# BG_Sch.net
KiCad netlist of a schematic drawn in Altium Designer
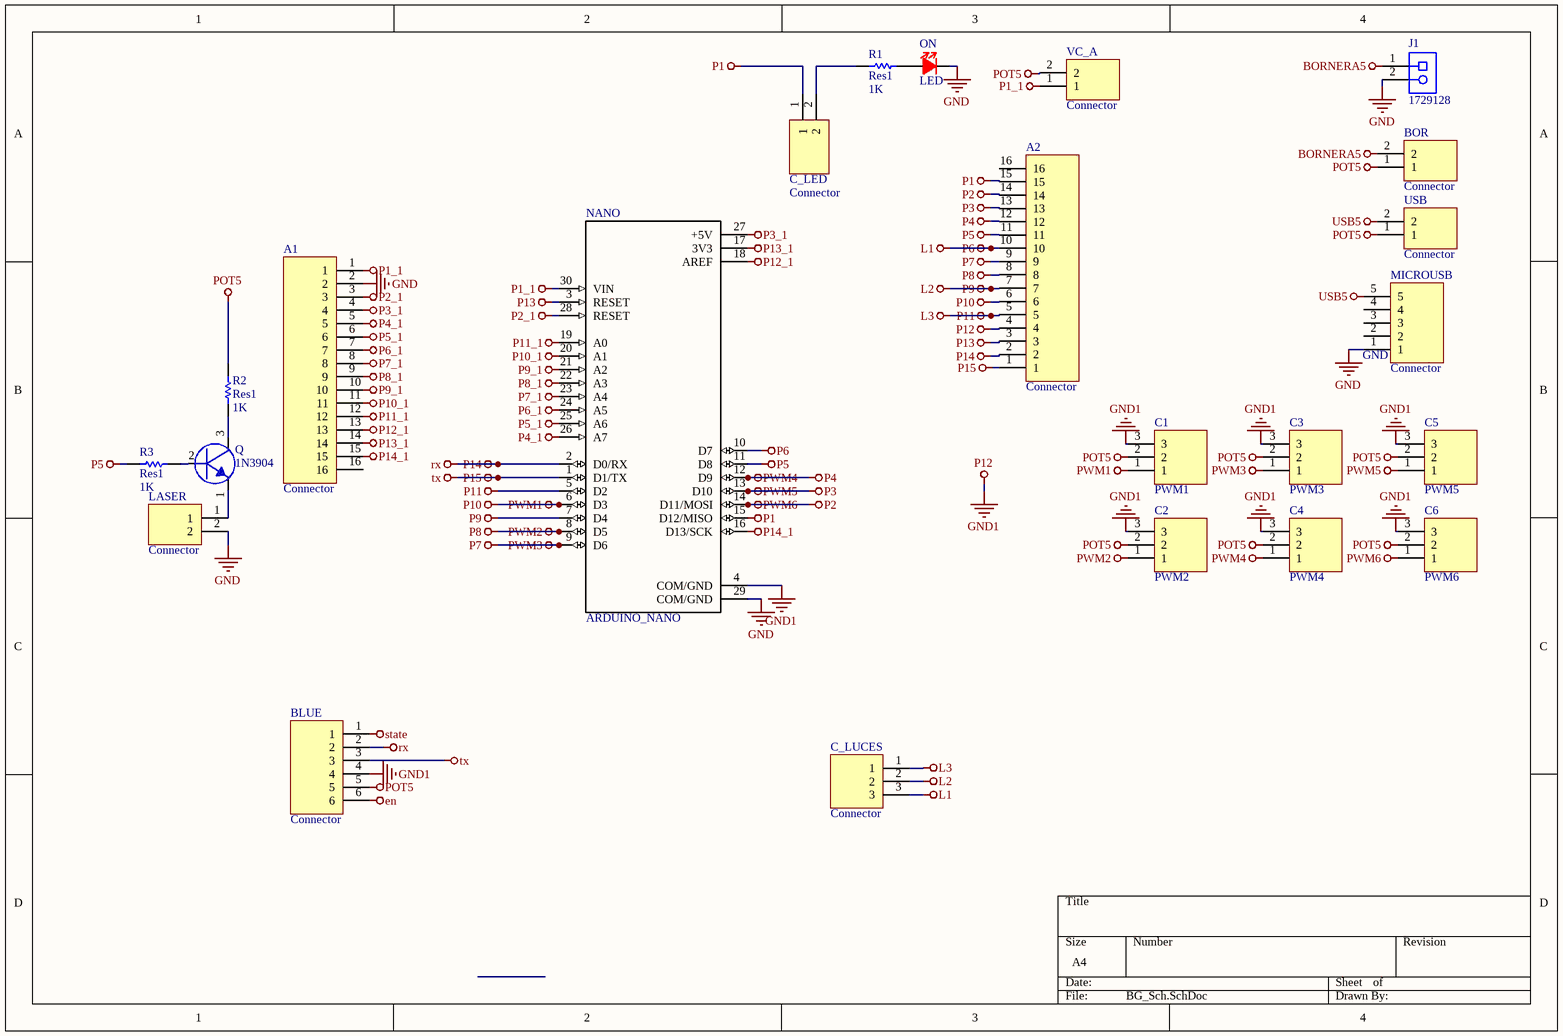
[diagram p0: BG_Sch.SchDoc]

(export (version "E")
  (design (tool "Eeschema 10.0.6"))
  (components
    (comp (ref "A1")
      (value "Connector")
      (footprint "1x16x2.54 Pin Header TH V")
      (libsource (lib "IFS_Altium") (part "Header 1x16"))
    )
    (comp (ref "A2")
      (value "Connector")
      (footprint "1x16x2.54 Pin Header TH V")
      (libsource (lib "") (part "Header 1x16_1"))
    )
    (comp (ref "BLUE")
      (value "Connector")
      (footprint "1x6x2.54 Pin Header TH V")
      (libsource (lib "IFS_Altium") (part "Header 1x6"))
    )
    (comp (ref "BOR")
      (value "Connector")
      (footprint "1x2x2.54 Pin Header TH V")
      (libsource (lib "IFS_Altium") (part "Header 1x2"))
    )
    (comp (ref "C1")
      (value "PWM1")
      (footprint "1x3x2.54 Pin Header TH V")
      (libsource (lib "IFS_Altium") (part "Header 1x3"))
    )
    (comp (ref "C2")
      (value "PWM2")
      (footprint "1x3x2.54 Pin Header TH V")
      (libsource (lib "IFS_Altium") (part "Header 1x3"))
    )
    (comp (ref "C3")
      (value "PWM3")
      (footprint "1x3x2.54 Pin Header TH V")
      (libsource (lib "IFS_Altium") (part "Header 1x3"))
    )
    (comp (ref "C4")
      (value "PWM4")
      (footprint "1x3x2.54 Pin Header TH V")
      (libsource (lib "IFS_Altium") (part "Header 1x3"))
    )
    (comp (ref "C5")
      (value "PWM5")
      (footprint "1x3x2.54 Pin Header TH V")
      (libsource (lib "IFS_Altium") (part "Header 1x3"))
    )
    (comp (ref "C6")
      (value "PWM6")
      (footprint "1x3x2.54 Pin Header TH V")
      (libsource (lib "IFS_Altium") (part "Header 1x3"))
    )
    (comp (ref "C_LED")
      (value "Connector")
      (footprint "1x2x2.54 Pin Header TH V")
      (libsource (lib "") (part "Header 1x2_1"))
    )
    (comp (ref "C_LUCES")
      (value "Connector")
      (footprint "1x3x2.54 Pin Header TH V")
      (libsource (lib "CARO") (part "Header 1x3"))
    )
    (comp (ref "J1")
      (value "1729128")
      (footprint "PHOE-1729128-2_V")
      (description "PCB Terminal Block, 13.5 A, 400 V, 2-Pin THD, RoHS, Bulk")
      (fields (field (name "MANUFACTURER") "Phoenix Contact"))
      (libsource (lib "Altium Content Vault") (part "CN-2P-F-R2"))
    )
    (comp (ref "LASER")
      (value "Connector")
      (footprint "1x2x2.54 Pin Header TH V")
      (libsource (lib "CARO") (part "Header 1x2"))
    )
    (comp (ref "MICROUSB")
      (value "Connector")
      (footprint "1x5x2.54 Pin Header TH V")
      (libsource (lib "IFS_Altium") (part "Header 1x5"))
    )
    (comp (ref "NANO")
      (value "ARDUINO_NANO")
      (footprint "*SHIELD_ARDUINO_NANO")
      (description "ATmega328 Arduino Nano AVRÂ® ATmega AVR MCU 8-Bit Embedded Evaluation Board")
      (fields (field (name "MP") "ARDUINO NANO") (field (name "MF") "Arduino"))
      (libsource (lib "Mercury") (part "ARDUINO_NANO"))
    )
    (comp (ref "ON")
      (value "LED")
      (footprint "LED Red 3mm TH V")
      (description "LED Red")
      (libsource (lib "IFS_Altium") (part "LED Red"))
    )
    (comp (ref "Q")
      (value "1N3904")
      (footprint "TO92-2.54")
      (description "1N3904 NPN Transistor")
      (libsource (lib "IFS_Altium") (part "1N3904"))
    )
    (comp (ref "R1")
      (value "Res1")
      (footprint "AXIAL-0.3")
      (description "Resistor")
      (fields (field (name "ALTIUM_VALUE") "1K") (field (name "PUBLISHER") "Altium Limited"))
      (libsource (lib "Miscellaneous Devices") (part "Res1"))
    )
    (comp (ref "R2")
      (value "Res1")
      (footprint "AXIAL-0.3")
      (description "Resistor")
      (fields (field (name "ALTIUM_VALUE") "1K") (field (name "PUBLISHER") "Altium Limited"))
      (libsource (lib "Miscellaneous Devices") (part "Res1"))
    )
    (comp (ref "R3")
      (value "Res1")
      (footprint "AXIAL-0.3")
      (description "Resistor")
      (fields (field (name "ALTIUM_VALUE") "1K") (field (name "PUBLISHER") "Altium Limited"))
      (libsource (lib "Miscellaneous Devices") (part "Res1"))
    )
    (comp (ref "USB")
      (value "Connector")
      (footprint "1x2x2.54 Pin Header TH V")
      (libsource (lib "IFS_Altium") (part "Header 1x2"))
    )
    (comp (ref "VC_A")
      (value "Connector")
      (footprint "1x2x2.54 Pin Header TH V")
      (libsource (lib "IFS_Altium") (part "Header 1x2"))
    )
  )
  (nets
    (net (code "1") (name "BORNERA5") (class "Default")
      (node (ref "BOR") (pin "2") (pinfunction "2_2") (pintype "passive"))
      (node (ref "J1") (pin "1") (pinfunction "1_1") (pintype "passive"))
    )
    (net (code "2") (name "GND") (class "Default")
      (node (ref "A1") (pin "2") (pinfunction "2_2") (pintype "passive"))
      (node (ref "J1") (pin "2") (pinfunction "2_2") (pintype "passive"))
      (node (ref "LASER") (pin "2") (pinfunction "2_2") (pintype "passive"))
      (node (ref "MICROUSB") (pin "1") (pinfunction "1_1") (pintype "passive"))
      (node (ref "NANO") (pin "29") (pinfunction "COM/GND_29") (pintype "power_in"))
      (node (ref "ON") (pin "1") (pinfunction "1_1") (pintype "passive"))
    )
    (net (code "3") (name "GND1") (class "Default")
      (node (ref "A2") (pin "4") (pinfunction "4_4") (pintype "passive"))
      (node (ref "BLUE") (pin "4") (pinfunction "4_4") (pintype "passive"))
      (node (ref "C1") (pin "3") (pinfunction "3_3") (pintype "passive"))
      (node (ref "C2") (pin "3") (pinfunction "3_3") (pintype "passive"))
      (node (ref "C3") (pin "3") (pinfunction "3_3") (pintype "passive"))
      (node (ref "C4") (pin "3") (pinfunction "3_3") (pintype "passive"))
      (node (ref "C5") (pin "3") (pinfunction "3_3") (pintype "passive"))
      (node (ref "C6") (pin "3") (pinfunction "3_3") (pintype "passive"))
      (node (ref "NANO") (pin "4") (pinfunction "COM/GND_4") (pintype "power_in"))
    )
    (net (code "4") (name "L1") (class "Default")
      (node (ref "A2") (pin "10") (pinfunction "10_10") (pintype "passive"))
      (node (ref "C_LUCES") (pin "3") (pinfunction "3_3") (pintype "passive"))
      (node (ref "NANO") (pin "10") (pinfunction "D7_10") (pintype "bidirectional"))
    )
    (net (code "5") (name "L2") (class "Default")
      (node (ref "A2") (pin "7") (pinfunction "7_7") (pintype "passive"))
      (node (ref "C_LUCES") (pin "2") (pinfunction "2_2") (pintype "passive"))
      (node (ref "NANO") (pin "7") (pinfunction "D4_7") (pintype "bidirectional"))
    )
    (net (code "6") (name "L3") (class "Default")
      (node (ref "A2") (pin "5") (pinfunction "5_5") (pintype "passive"))
      (node (ref "C_LUCES") (pin "1") (pinfunction "1_1") (pintype "passive"))
      (node (ref "NANO") (pin "5") (pinfunction "D2_5") (pintype "bidirectional"))
    )
    (net (code "7") (name "Net-(C_LED-Pad2)") (class "Default")
      (node (ref "C_LED") (pin "2") (pinfunction "2_2") (pintype "passive"))
      (node (ref "R1") (pin "1") (pinfunction "1_1") (pintype "passive"))
    )
    (net (code "8") (name "Net-(LASER-Pad1)") (class "Default")
      (node (ref "LASER") (pin "1") (pinfunction "1_1") (pintype "passive"))
      (node (ref "Q") (pin "1") (pinfunction "1_1") (pintype "passive"))
    )
    (net (code "9") (name "Net-(ON-Pad2)") (class "Default")
      (node (ref "ON") (pin "2") (pinfunction "2_2") (pintype "passive"))
      (node (ref "R1") (pin "2") (pinfunction "2_2") (pintype "passive"))
    )
    (net (code "10") (name "Net-(Q-Pad2)") (class "Default")
      (node (ref "Q") (pin "2") (pinfunction "2_2") (pintype "passive"))
      (node (ref "R3") (pin "2") (pinfunction "2_2") (pintype "passive"))
    )
    (net (code "11") (name "Net-(Q-Pad3)") (class "Default")
      (node (ref "Q") (pin "3") (pinfunction "3_3") (pintype "passive"))
      (node (ref "R2") (pin "1") (pinfunction "1_1") (pintype "passive"))
    )
    (net (code "12") (name "P1") (class "Default")
      (node (ref "A2") (pin "15") (pinfunction "15_15") (pintype "passive"))
      (node (ref "C_LED") (pin "1") (pinfunction "1_1") (pintype "passive"))
      (node (ref "NANO") (pin "15") (pinfunction "D12/MISO_15") (pintype "bidirectional"))
    )
    (net (code "13") (name "P1_1") (class "Default")
      (node (ref "A1") (pin "1") (pinfunction "1_1") (pintype "passive"))
      (node (ref "NANO") (pin "30") (pinfunction "VIN_30") (pintype "input"))
      (node (ref "VC_A") (pin "1") (pinfunction "1_1") (pintype "passive"))
    )
    (net (code "14") (name "P2") (class "Default")
      (node (ref "A2") (pin "14") (pinfunction "14_14") (pintype "passive"))
      (node (ref "C6") (pin "1") (pinfunction "1_1") (pintype "passive"))
      (node (ref "NANO") (pin "14") (pinfunction "D11/MOSI_14") (pintype "bidirectional"))
    )
    (net (code "15") (name "P2_1") (class "Default")
      (node (ref "A1") (pin "3") (pinfunction "3_3") (pintype "passive"))
      (node (ref "NANO") (pin "28") (pinfunction "RESET_28") (pintype "input"))
    )
    (net (code "16") (name "P3") (class "Default")
      (node (ref "A2") (pin "13") (pinfunction "13_13") (pintype "passive"))
      (node (ref "C5") (pin "1") (pinfunction "1_1") (pintype "passive"))
      (node (ref "NANO") (pin "13") (pinfunction "D10_13") (pintype "bidirectional"))
    )
    (net (code "17") (name "P3_1") (class "Default")
      (node (ref "A1") (pin "4") (pinfunction "4_4") (pintype "passive"))
      (node (ref "NANO") (pin "27") (pinfunction "+5V_27") (pintype "power_in"))
    )
    (net (code "18") (name "P4") (class "Default")
      (node (ref "A2") (pin "12") (pinfunction "12_12") (pintype "passive"))
      (node (ref "C4") (pin "1") (pinfunction "1_1") (pintype "passive"))
      (node (ref "NANO") (pin "12") (pinfunction "D9_12") (pintype "bidirectional"))
    )
    (net (code "19") (name "P4_1") (class "Default")
      (node (ref "A1") (pin "5") (pinfunction "5_5") (pintype "passive"))
      (node (ref "NANO") (pin "26") (pinfunction "A7_26") (pintype "input"))
    )
    (net (code "20") (name "P5") (class "Default")
      (node (ref "A2") (pin "11") (pinfunction "11_11") (pintype "passive"))
      (node (ref "NANO") (pin "11") (pinfunction "D8_11") (pintype "bidirectional"))
      (node (ref "R3") (pin "1") (pinfunction "1_1") (pintype "passive"))
    )
    (net (code "21") (name "P5_1") (class "Default")
      (node (ref "A1") (pin "6") (pinfunction "6_6") (pintype "passive"))
      (node (ref "NANO") (pin "25") (pinfunction "A6_25") (pintype "input"))
    )
    (net (code "22") (name "P6_1") (class "Default")
      (node (ref "A1") (pin "7") (pinfunction "7_7") (pintype "passive"))
      (node (ref "NANO") (pin "24") (pinfunction "A5_24") (pintype "input"))
    )
    (net (code "23") (name "P7") (class "Default")
      (node (ref "A2") (pin "9") (pinfunction "9_9") (pintype "passive"))
      (node (ref "C3") (pin "1") (pinfunction "1_1") (pintype "passive"))
      (node (ref "NANO") (pin "9") (pinfunction "D6_9") (pintype "bidirectional"))
    )
    (net (code "24") (name "P7_1") (class "Default")
      (node (ref "A1") (pin "8") (pinfunction "8_8") (pintype "passive"))
      (node (ref "NANO") (pin "23") (pinfunction "A4_23") (pintype "input"))
    )
    (net (code "25") (name "P8") (class "Default")
      (node (ref "A2") (pin "8") (pinfunction "8_8") (pintype "passive"))
      (node (ref "C2") (pin "1") (pinfunction "1_1") (pintype "passive"))
      (node (ref "NANO") (pin "8") (pinfunction "D5_8") (pintype "bidirectional"))
    )
    (net (code "26") (name "P8_1") (class "Default")
      (node (ref "A1") (pin "9") (pinfunction "9_9") (pintype "passive"))
      (node (ref "NANO") (pin "22") (pinfunction "A3_22") (pintype "input"))
    )
    (net (code "27") (name "P9_1") (class "Default")
      (node (ref "A1") (pin "10") (pinfunction "10_10") (pintype "passive"))
      (node (ref "NANO") (pin "21") (pinfunction "A2_21") (pintype "input"))
    )
    (net (code "28") (name "P10") (class "Default")
      (node (ref "A2") (pin "6") (pinfunction "6_6") (pintype "passive"))
      (node (ref "C1") (pin "1") (pinfunction "1_1") (pintype "passive"))
      (node (ref "NANO") (pin "6") (pinfunction "D3_6") (pintype "bidirectional"))
    )
    (net (code "29") (name "P10_1") (class "Default")
      (node (ref "A1") (pin "11") (pinfunction "11_11") (pintype "passive"))
      (node (ref "NANO") (pin "20") (pinfunction "A1_20") (pintype "input"))
    )
    (net (code "30") (name "P11_1") (class "Default")
      (node (ref "A1") (pin "12") (pinfunction "12_12") (pintype "passive"))
      (node (ref "NANO") (pin "19") (pinfunction "A0_19") (pintype "input"))
    )
    (net (code "31") (name "P12_1") (class "Default")
      (node (ref "A1") (pin "13") (pinfunction "13_13") (pintype "passive"))
      (node (ref "NANO") (pin "18") (pinfunction "AREF_18") (pintype "power_in"))
    )
    (net (code "32") (name "P13") (class "Default")
      (node (ref "A2") (pin "3") (pinfunction "3_3") (pintype "passive"))
      (node (ref "NANO") (pin "3") (pinfunction "RESET_3") (pintype "input"))
    )
    (net (code "33") (name "P13_1") (class "Default")
      (node (ref "A1") (pin "14") (pinfunction "14_14") (pintype "passive"))
      (node (ref "NANO") (pin "17") (pinfunction "3V3_17") (pintype "power_in"))
    )
    (net (code "34") (name "P14") (class "Default")
      (node (ref "A2") (pin "2") (pinfunction "2_2") (pintype "passive"))
      (node (ref "BLUE") (pin "2") (pinfunction "2_2") (pintype "passive"))
      (node (ref "NANO") (pin "2") (pinfunction "D0/RX_2") (pintype "bidirectional"))
    )
    (net (code "35") (name "P14_1") (class "Default")
      (node (ref "A1") (pin "15") (pinfunction "15_15") (pintype "passive"))
      (node (ref "NANO") (pin "16") (pinfunction "D13/SCK_16") (pintype "bidirectional"))
    )
    (net (code "36") (name "P15") (class "Default")
      (node (ref "A2") (pin "1") (pinfunction "1_1") (pintype "passive"))
      (node (ref "BLUE") (pin "3") (pinfunction "3_3") (pintype "passive"))
      (node (ref "NANO") (pin "1") (pinfunction "D1/TX_1") (pintype "bidirectional"))
    )
    (net (code "37") (name "POT5") (class "Default")
      (node (ref "BLUE") (pin "5") (pinfunction "5_5") (pintype "passive"))
      (node (ref "BOR") (pin "1") (pinfunction "1_1") (pintype "passive"))
      (node (ref "C1") (pin "2") (pinfunction "2_2") (pintype "passive"))
      (node (ref "C2") (pin "2") (pinfunction "2_2") (pintype "passive"))
      (node (ref "C3") (pin "2") (pinfunction "2_2") (pintype "passive"))
      (node (ref "C4") (pin "2") (pinfunction "2_2") (pintype "passive"))
      (node (ref "C5") (pin "2") (pinfunction "2_2") (pintype "passive"))
      (node (ref "C6") (pin "2") (pinfunction "2_2") (pintype "passive"))
      (node (ref "R2") (pin "2") (pinfunction "2_2") (pintype "passive"))
      (node (ref "USB") (pin "1") (pinfunction "1_1") (pintype "passive"))
      (node (ref "VC_A") (pin "2") (pinfunction "2_2") (pintype "passive"))
    )
    (net (code "38") (name "USB5") (class "Default")
      (node (ref "MICROUSB") (pin "5") (pinfunction "5_5") (pintype "passive"))
      (node (ref "USB") (pin "2") (pinfunction "2_2") (pintype "passive"))
    )
    (net (code "39") (name "en") (class "Default")
      (node (ref "BLUE") (pin "6") (pinfunction "6_6") (pintype "passive"))
    )
    (net (code "40") (name "state") (class "Default")
      (node (ref "BLUE") (pin "1") (pinfunction "1_1") (pintype "passive"))
    )
    (net (code "41") (name "unconnected-(A1-Pad16)") (class "Default")
      (node (ref "A1") (pin "16") (pinfunction "16_16") (pintype "passive"))
    )
    (net (code "42") (name "unconnected-(A2-Pad16)") (class "Default")
      (node (ref "A2") (pin "16") (pinfunction "16_16") (pintype "passive"))
    )
    (net (code "43") (name "unconnected-(MICROUSB-Pad2)") (class "Default")
      (node (ref "MICROUSB") (pin "2") (pinfunction "2_2") (pintype "passive"))
    )
    (net (code "44") (name "unconnected-(MICROUSB-Pad3)") (class "Default")
      (node (ref "MICROUSB") (pin "3") (pinfunction "3_3") (pintype "passive"))
    )
    (net (code "45") (name "unconnected-(MICROUSB-Pad4)") (class "Default")
      (node (ref "MICROUSB") (pin "4") (pinfunction "4_4") (pintype "passive"))
    )
  )
)
